# eagleExperiment3.net
KiCad netlist of a schematic drawn in EAGLE
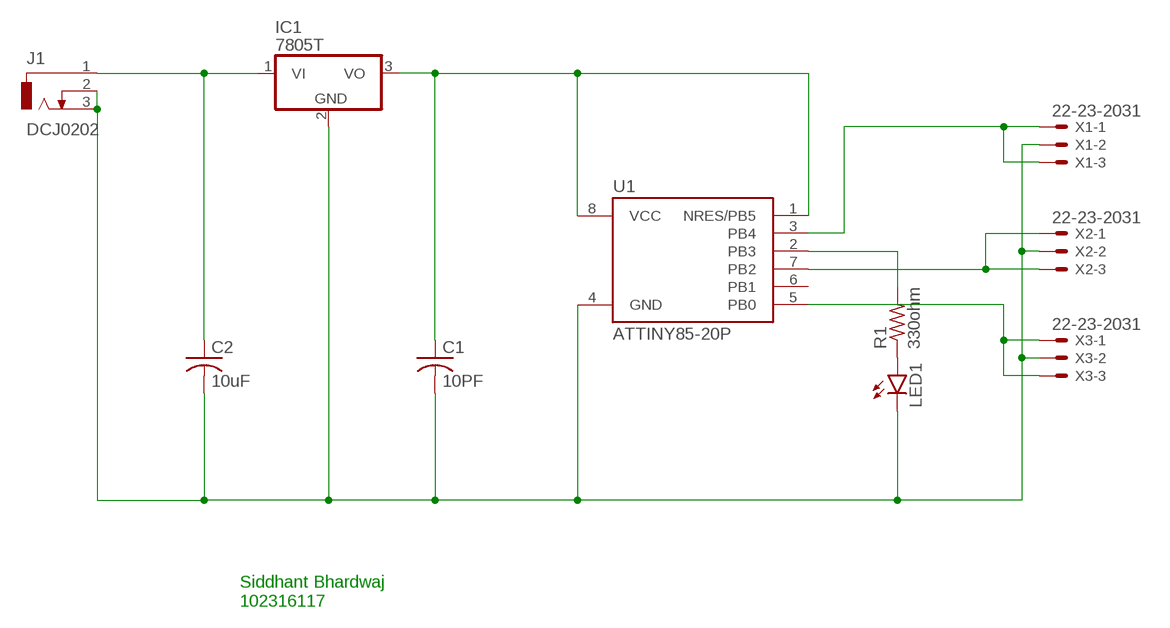
[diagram p0: schematic, sheet 1]

(export (version "E")
  (design (tool "Eeschema 10.0.6"))
  (components
    (comp (ref "C1")
      (value "10PF")
      (footprint "eagle-import:C025-024X044")
      (libsource (lib "eagle-import") (part "C-US025-024X044"))
    )
    (comp (ref "C2")
      (value "10uF")
      (footprint "eagle-import:C025-024X044")
      (libsource (lib "eagle-import") (part "C-US025-024X044"))
    )
    (comp (ref "IC1")
      (value "7805T")
      (footprint "eagle-import:TO220H")
      (libsource (lib "eagle-import") (part "78T05"))
    )
    (comp (ref "J1")
      (value "DCJ0202")
      (footprint "eagle-import:DCJ0202")
      (libsource (lib "eagle-import") (part "DCJ0202"))
    )
    (comp (ref "LED1")
      (value "LED3MM")
      (footprint "eagle-import:LED3MM")
      (libsource (lib "eagle-import") (part "LED3MM"))
    )
    (comp (ref "R1")
      (value "330ohm")
      (footprint "eagle-import:0207_5V")
      (libsource (lib "eagle-import") (part "R-US_0207/5V"))
    )
    (comp (ref "U1")
      (value "ATTINY85-20P")
      (footprint "eagle-import:PDIP08_300MIL")
      (libsource (lib "eagle-import") (part "ATTINY85P-20"))
    )
    (comp (ref "X1")
      (value "22-23-2031")
      (footprint "eagle-import:22-23-2031")
      (fields (field (name "MF") "MOLEX"))
      (libsource (lib "eagle-import") (part "22-23-2031"))
    )
    (comp (ref "X2")
      (value "22-23-2031")
      (footprint "eagle-import:22-23-2031")
      (fields (field (name "MF") "MOLEX"))
      (libsource (lib "eagle-import") (part "22-23-2031"))
    )
    (comp (ref "X3")
      (value "22-23-2031")
      (footprint "eagle-import:22-23-2031")
      (fields (field (name "MF") "MOLEX"))
      (libsource (lib "eagle-import") (part "22-23-2031"))
    )
  )
  (nets
    (net (code "1") (name "Net-(IC1-GND)") (class "Default")
      (node (ref "C1") (pin "2") (pinfunction "2_2") (pintype "passive"))
      (node (ref "C2") (pin "2") (pinfunction "2_2") (pintype "passive"))
      (node (ref "IC1") (pin "2") (pinfunction "GND_2") (pintype "passive"))
      (node (ref "J1") (pin "2") (pinfunction "2_2") (pintype "passive"))
      (node (ref "J1") (pin "3") (pinfunction "3_3") (pintype "passive"))
      (node (ref "LED1") (pin "K") (pinfunction "C_K") (pintype "passive"))
      (node (ref "U1") (pin "4") (pinfunction "GND_4") (pintype "power_in"))
      (node (ref "X1") (pin "2") (pinfunction "S_2") (pintype "passive"))
      (node (ref "X2") (pin "2") (pinfunction "S_2") (pintype "passive"))
      (node (ref "X3") (pin "2") (pinfunction "S_2") (pintype "passive"))
    )
    (net (code "2") (name "Net-(IC1-VI)") (class "Default")
      (node (ref "C2") (pin "1") (pinfunction "1_1") (pintype "passive"))
      (node (ref "IC1") (pin "1") (pinfunction "VI_1") (pintype "input"))
      (node (ref "J1") (pin "1") (pinfunction "1_1") (pintype "passive"))
    )
    (net (code "3") (name "Net-(IC1-VO)") (class "Default")
      (node (ref "C1") (pin "1") (pinfunction "1_1") (pintype "passive"))
      (node (ref "IC1") (pin "3") (pinfunction "VO_3") (pintype "passive"))
      (node (ref "U1") (pin "1") (pinfunction "NRES/PB5_1") (pintype "bidirectional"))
      (node (ref "U1") (pin "8") (pinfunction "VCC_8") (pintype "power_in"))
    )
    (net (code "4") (name "Net-(LED1-PadA)") (class "Default")
      (node (ref "LED1") (pin "A") (pinfunction "A_A") (pintype "passive"))
      (node (ref "R1") (pin "1") (pinfunction "1_1") (pintype "passive"))
    )
    (net (code "5") (name "Net-(U1-PB0)") (class "Default")
      (node (ref "U1") (pin "5") (pinfunction "PB0_5") (pintype "bidirectional"))
      (node (ref "X3") (pin "1") (pinfunction "S_1") (pintype "passive"))
      (node (ref "X3") (pin "3") (pinfunction "S_3") (pintype "passive"))
    )
    (net (code "6") (name "Net-(U1-PB2)") (class "Default")
      (node (ref "U1") (pin "7") (pinfunction "PB2_7") (pintype "bidirectional"))
      (node (ref "X2") (pin "1") (pinfunction "S_1") (pintype "passive"))
      (node (ref "X2") (pin "3") (pinfunction "S_3") (pintype "passive"))
    )
    (net (code "7") (name "Net-(U1-PB3)") (class "Default")
      (node (ref "R1") (pin "2") (pinfunction "2_2") (pintype "passive"))
      (node (ref "U1") (pin "2") (pinfunction "PB3_2") (pintype "bidirectional"))
    )
    (net (code "8") (name "Net-(U1-PB4)") (class "Default")
      (node (ref "U1") (pin "3") (pinfunction "PB4_3") (pintype "bidirectional"))
      (node (ref "X1") (pin "1") (pinfunction "S_1") (pintype "passive"))
      (node (ref "X1") (pin "3") (pinfunction "S_3") (pintype "passive"))
    )
    (net (code "9") (name "unconnected-(U1-PB1-Pad6)") (class "Default")
      (node (ref "U1") (pin "6") (pinfunction "PB1_6") (pintype "bidirectional"))
    )
  )
)
